# TM_Conditioning.net
KiCad netlist of a schematic drawn in Altium Designer
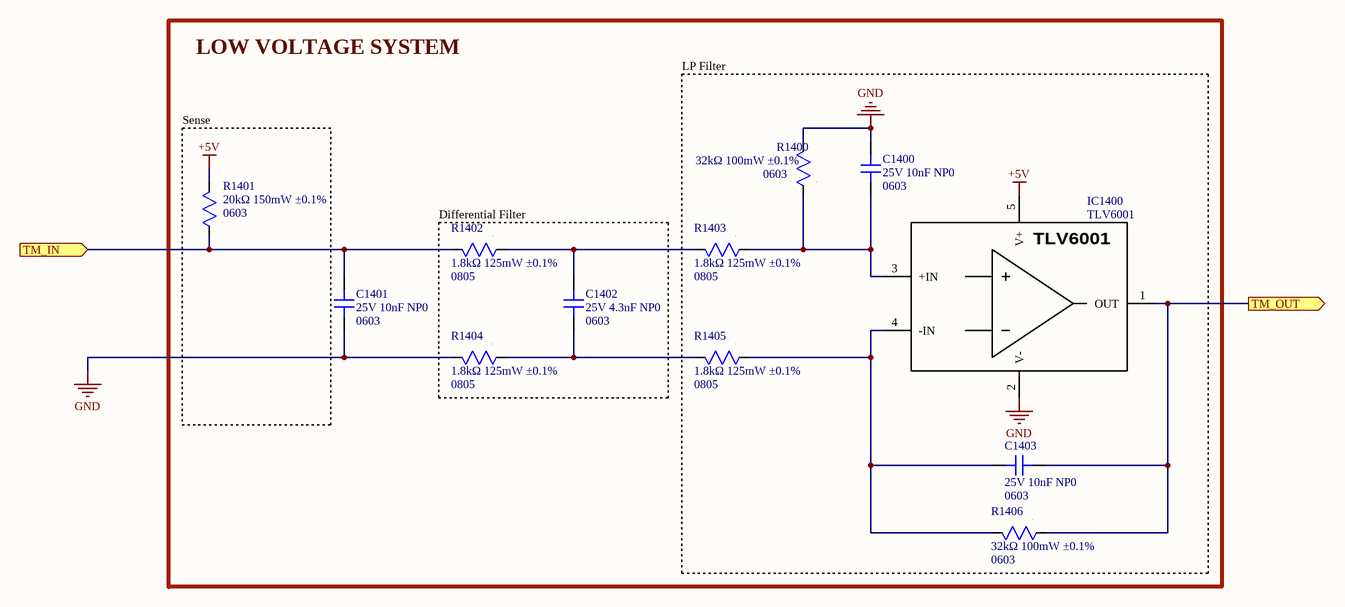
[diagram p0: TM_Conditioning.SchDoc]

(export (version "E")
  (design (tool "Eeschema 10.0.6"))
  (components
    (comp (ref "C1400")
      (value "25V 10nF NP0")
      (footprint "CAP SMD 0603")
      (description "Condensadores de cerámica multicapa (MLCC- SMD/SMT) 0.01 uF 25 VDC 1% 0603 C0G (NP0) AEC-Q200")
      (fields
        (field (name "PACKAGE") "0603")
        (field (name "MPN") "GRT1885C1E103FA02D")
        (field (name "MANUFACTURER") "muRata")
      )
      (libsource (lib "eUSR_Database") (part "CAP non polarized"))
    )
    (comp (ref "C1401")
      (value "25V 10nF NP0")
      (footprint "CAP SMD 0603")
      (description "Condensadores de cerámica multicapa (MLCC- SMD/SMT) 50V 5100pF 0603 C0G 1%")
      (fields
        (field (name "PACKAGE") "0603")
        (field (name "MPN") "C0603C512F5GACTU")
        (field (name "MANUFACTURER") "KEMET")
      )
      (libsource (lib "eUSR_Database") (part "CAP non polarized"))
    )
    (comp (ref "C1402")
      (value "25V 4.3nF NP0")
      (footprint "CAP SMD 0603")
      (description "Condensadores de cerámica multicapa (MLCC- SMD/SMT) 4300 pF 25 VDC 2% 0603 C0G (NP0)")
      (fields
        (field (name "PACKAGE") "0603")
        (field (name "MPN") "GRM1885C1E432GA01J")
        (field (name "MANUFACTURER") "muRata")
      )
      (libsource (lib "eUSR_Database") (part "CAP non polarized"))
    )
    (comp (ref "C1403")
      (value "25V 10nF NP0")
      (footprint "CAP SMD 0603")
      (description "Condensadores de cerámica multicapa (MLCC- SMD/SMT) 0.01 uF 25 VDC 1% 0603 C0G (NP0) AEC-Q200")
      (fields
        (field (name "PACKAGE") "0603")
        (field (name "MPN") "GRT1885C1E103FA02D")
        (field (name "MANUFACTURER") "muRata")
      )
      (libsource (lib "eUSR_Database") (part "CAP non polarized"))
    )
    (comp (ref "IC1400")
      (value "TLV6001")
      (footprint "SOT-23-5")
      (fields (field (name "MPN") "TLV6001UIDBVR") (field (name "MANUFACTURER") "Texas Instruments"))
      (libsource (lib "eUSR_Database") (part "TLV6001"))
    )
    (comp (ref "R1400")
      (value "32kΩ 100mW ±0.1%")
      (footprint "RES SMD 0603")
      (description "Resistores de película fina - SMD 1/10W 32K Ohms 0.1%")
      (fields
        (field (name "PACKAGE") "0603")
        (field (name "MPN") "RT0603BRD0732KL")
        (field (name "MANUFACTURER") "YAGEO")
      )
      (libsource (lib "eUSR_Database") (part "RES"))
    )
    (comp (ref "R1401")
      (value "20kΩ 150mW ±0.1%")
      (footprint "RES SMD 0603")
      (description "Resistores de película fina - SMD RQ 0603 20K 0.1% 10PPM 5K RL")
      (fields
        (field (name "PACKAGE") "0603")
        (field (name "MPN") "RQ73C1J20KBTD")
        (field (name "MANUFACTURER") "TE Connectivity / Holsworthy")
      )
      (libsource (lib "eUSR_Database") (part "RES"))
    )
    (comp (ref "R1402")
      (value "1.8kΩ 125mW ±0.1%")
      (footprint "RES SMD 0805")
      (description "Thin Film Resistors 0805 1.8Kohm 0.1% 10ppm AEC-Q200")
      (fields
        (field (name "PACKAGE") "0805")
        (field (name "MPN") "ERA-6ARB182V")
        (field (name "MANUFACTURER") "Panasonic")
      )
      (libsource (lib "eUSR_Database") (part "RES"))
    )
    (comp (ref "R1403")
      (value "1.8kΩ 125mW ±0.1%")
      (footprint "RES SMD 0805")
      (description "Thin Film Resistors 0805 1.8Kohm 0.1% 10ppm AEC-Q200")
      (fields
        (field (name "PACKAGE") "0805")
        (field (name "MPN") "ERA-6ARB182V")
        (field (name "MANUFACTURER") "Panasonic")
      )
      (libsource (lib "eUSR_Database") (part "RES"))
    )
    (comp (ref "R1404")
      (value "1.8kΩ 125mW ±0.1%")
      (footprint "RES SMD 0805")
      (description "Thin Film Resistors 0805 1.8Kohm 0.1% 10ppm AEC-Q200")
      (fields
        (field (name "PACKAGE") "0805")
        (field (name "MPN") "ERA-6ARB182V")
        (field (name "MANUFACTURER") "Panasonic")
      )
      (libsource (lib "eUSR_Database") (part "RES"))
    )
    (comp (ref "R1405")
      (value "1.8kΩ 125mW ±0.1%")
      (footprint "RES SMD 0805")
      (description "Thin Film Resistors 0805 1.8Kohm 0.1% 10ppm AEC-Q200")
      (fields
        (field (name "PACKAGE") "0805")
        (field (name "MPN") "ERA-6ARB182V")
        (field (name "MANUFACTURER") "Panasonic")
      )
      (libsource (lib "eUSR_Database") (part "RES"))
    )
    (comp (ref "R1406")
      (value "32kΩ 100mW ±0.1%")
      (footprint "RES SMD 0603")
      (description "Resistores de película fina - SMD 1/10W 32K Ohms 0.1%")
      (fields
        (field (name "PACKAGE") "0603")
        (field (name "MPN") "RT0603BRD0732KL")
        (field (name "MANUFACTURER") "YAGEO")
      )
      (libsource (lib "eUSR_Database") (part "RES"))
    )
  )
  (nets
    (net (code "1") (name "+5V") (class "Default")
      (node (ref "IC1400") (pin "5") (pinfunction "V+_5") (pintype "passive"))
      (node (ref "R1401") (pin "2") (pinfunction "2_2") (pintype "passive"))
    )
    (net (code "2") (name "/TM_IN") (class "Default")
      (node (ref "C1401") (pin "1") (pinfunction "1_1") (pintype "passive"))
      (node (ref "R1401") (pin "1") (pinfunction "1_1") (pintype "passive"))
      (node (ref "R1402") (pin "2") (pinfunction "2_2") (pintype "passive"))
    )
    (net (code "3") (name "/TM_OUT") (class "Default")
      (node (ref "C1403") (pin "2") (pinfunction "2_2") (pintype "passive"))
      (node (ref "IC1400") (pin "1") (pinfunction "OUT_1") (pintype "passive"))
      (node (ref "R1406") (pin "1") (pinfunction "1_1") (pintype "passive"))
    )
    (net (code "4") (name "GND") (class "Default")
      (node (ref "C1400") (pin "2") (pinfunction "2_2") (pintype "passive"))
      (node (ref "C1401") (pin "2") (pinfunction "2_2") (pintype "passive"))
      (node (ref "IC1400") (pin "2") (pinfunction "V-_2") (pintype "passive"))
      (node (ref "R1400") (pin "2") (pinfunction "2_2") (pintype "passive"))
      (node (ref "R1404") (pin "2") (pinfunction "2_2") (pintype "passive"))
    )
    (net (code "5") (name "Net-(C1402-Pad1)") (class "Default")
      (node (ref "C1402") (pin "1") (pinfunction "1_1") (pintype "passive"))
      (node (ref "R1402") (pin "1") (pinfunction "1_1") (pintype "passive"))
      (node (ref "R1403") (pin "2") (pinfunction "2_2") (pintype "passive"))
    )
    (net (code "6") (name "Net-(C1402-Pad2)") (class "Default")
      (node (ref "C1402") (pin "2") (pinfunction "2_2") (pintype "passive"))
      (node (ref "R1404") (pin "1") (pinfunction "1_1") (pintype "passive"))
      (node (ref "R1405") (pin "2") (pinfunction "2_2") (pintype "passive"))
    )
    (net (code "7") (name "Net-(IC1400-+IN)") (class "Default")
      (node (ref "C1400") (pin "1") (pinfunction "1_1") (pintype "passive"))
      (node (ref "IC1400") (pin "3") (pinfunction "+IN_3") (pintype "passive"))
      (node (ref "R1400") (pin "1") (pinfunction "1_1") (pintype "passive"))
      (node (ref "R1403") (pin "1") (pinfunction "1_1") (pintype "passive"))
    )
    (net (code "8") (name "Net-(IC1400--IN)") (class "Default")
      (node (ref "C1403") (pin "1") (pinfunction "1_1") (pintype "passive"))
      (node (ref "IC1400") (pin "4") (pinfunction "-IN_4") (pintype "passive"))
      (node (ref "R1405") (pin "1") (pinfunction "1_1") (pintype "passive"))
      (node (ref "R1406") (pin "2") (pinfunction "2_2") (pintype "passive"))
    )
  )
)
